# sensor-mega169a.net
KiCad netlist of a schematic drawn in EAGLE
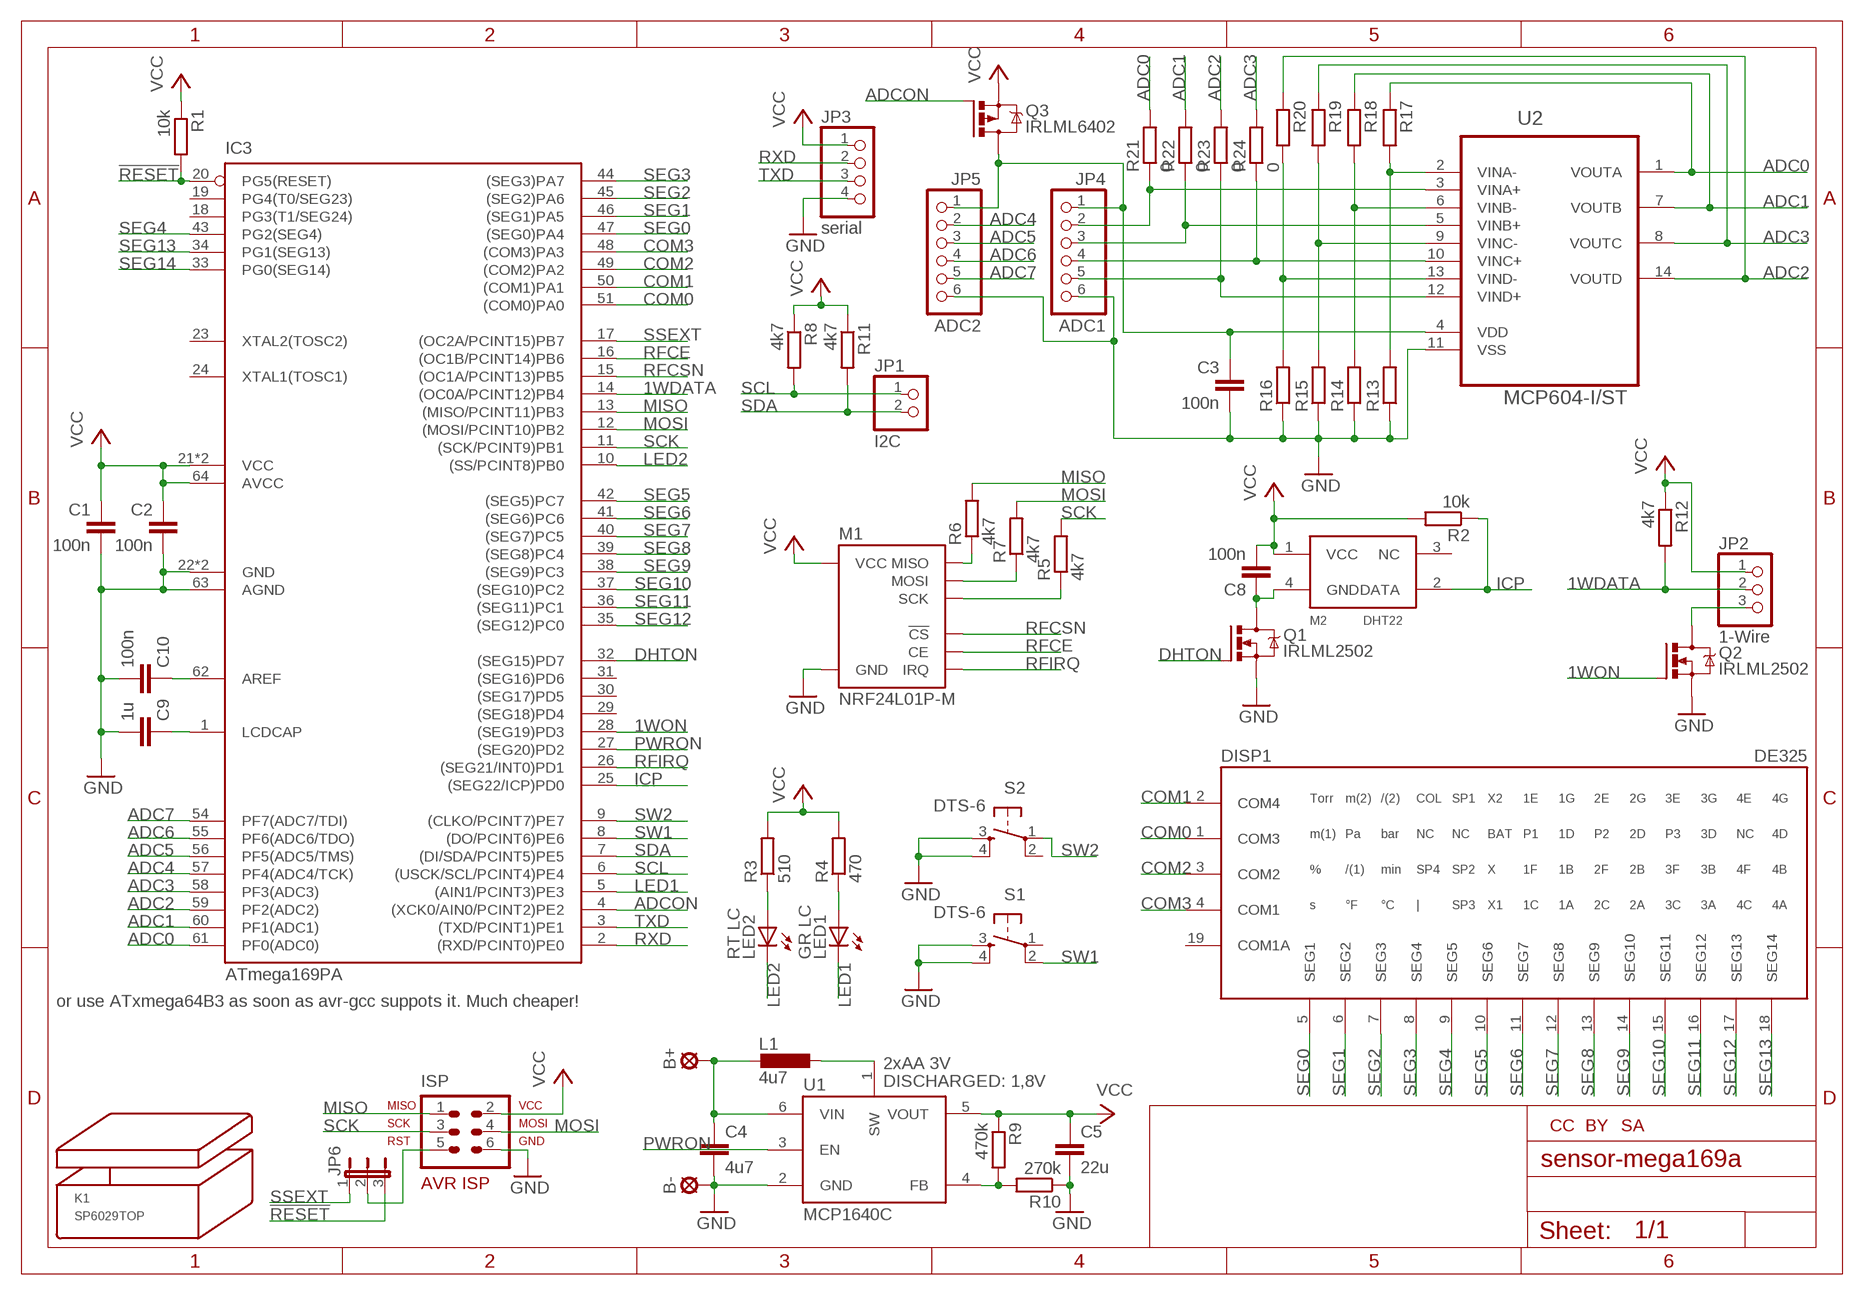
[diagram p0: schematic, sheet 1]

(export (version "E")
  (design (tool "Eeschema 10.0.6"))
  (components
    (comp (ref "B+")
      (value "LSP11")
      (footprint "eagle-import:LSP11")
      (libsource (lib "eagle-import") (part "LSP11"))
    )
    (comp (ref "B-")
      (value "LSP11")
      (footprint "eagle-import:LSP11")
      (libsource (lib "eagle-import") (part "LSP11"))
    )
    (comp (ref "C1")
      (value "100n")
      (footprint "eagle-import:C0603")
      (libsource (lib "eagle-import") (part "C-EUC0603"))
    )
    (comp (ref "C2")
      (value "100n")
      (footprint "eagle-import:C0603")
      (libsource (lib "eagle-import") (part "C-EUC0603"))
    )
    (comp (ref "C3")
      (value "100n")
      (footprint "eagle-import:C0603")
      (libsource (lib "eagle-import") (part "C-EUC0603"))
    )
    (comp (ref "C4")
      (value "4u7")
      (footprint "eagle-import:C0805")
      (libsource (lib "eagle-import") (part "C-EUC0805"))
    )
    (comp (ref "C5")
      (value "22u")
      (footprint "eagle-import:C1206")
      (libsource (lib "eagle-import") (part "C-EUC1206"))
    )
    (comp (ref "C8")
      (value "100n")
      (footprint "eagle-import:C0603")
      (libsource (lib "eagle-import") (part "C-EUC0603"))
    )
    (comp (ref "C9")
      (value "1u")
      (footprint "eagle-import:C0603")
      (libsource (lib "eagle-import") (part "C-EUC0603"))
    )
    (comp (ref "C10")
      (value "100n")
      (footprint "eagle-import:C0603")
      (libsource (lib "eagle-import") (part "C-EUC0603"))
    )
    (comp (ref "DISP1")
      (value "DE325")
      (footprint "eagle-import:DE325")
      (libsource (lib "eagle-import") (part "DE325"))
    )
    (comp (ref "IC3")
      (value "ATmega169PA")
      (footprint "eagle-import:TQFP64")
      (libsource (lib "eagle-import") (part "MEGA169-A"))
    )
    (comp (ref "ISP")
      (value "ML6")
      (footprint "eagle-import:AVR-ISP-6")
      (libsource (lib "eagle-import") (part "AVR-ISP-6VERT"))
    )
    (comp (ref "JP1")
      (value "I2C")
      (footprint "eagle-import:1X02")
      (libsource (lib "eagle-import") (part "PINHD-1X2_2.54"))
    )
    (comp (ref "JP2")
      (value "1-Wire")
      (footprint "eagle-import:1X03")
      (libsource (lib "eagle-import") (part "PINHD-1X3_2.54"))
    )
    (comp (ref "JP3")
      (value "serial")
      (footprint "eagle-import:1X04")
      (libsource (lib "eagle-import") (part "PINHD-1X4_2.54"))
    )
    (comp (ref "JP4")
      (value "ADC1")
      (footprint "eagle-import:1X06")
      (libsource (lib "eagle-import") (part "PINHD-1X6_2.54"))
    )
    (comp (ref "JP5")
      (value "ADC2")
      (footprint "eagle-import:1X06")
      (libsource (lib "eagle-import") (part "PINHD-1X6_2.54"))
    )
    (comp (ref "JP6")
      (value "JP2E")
      (footprint "eagle-import:JP2")
      (libsource (lib "eagle-import") (part "JP2E"))
    )
    (comp (ref "K1")
      (value "SP6029TOP")
      (footprint "eagle-import:SP6029T")
      (libsource (lib "eagle-import") (part "SP6029TOP"))
    )
    (comp (ref "L1")
      (value "4u7")
      (footprint "eagle-import:PISG")
      (libsource (lib "eagle-import") (part "L-EUPISG"))
    )
    (comp (ref "LED1")
      (value "GR LC")
      (footprint "eagle-import:LED5MM")
      (libsource (lib "eagle-import") (part "LED5MM"))
    )
    (comp (ref "LED2")
      (value "RT LC")
      (footprint "eagle-import:LED5MM")
      (libsource (lib "eagle-import") (part "LED5MM"))
    )
    (comp (ref "M1")
      (value "NRF24L01P-M")
      (footprint "eagle-import:NRF24L01P-A")
      (libsource (lib "eagle-import") (part "NRF24L01P-M"))
    )
    (comp (ref "M2")
      (value "DHT22")
      (footprint "eagle-import:DHT22")
      (libsource (lib "eagle-import") (part "DHT22"))
    )
    (comp (ref "Q1")
      (value "IRLML2502")
      (footprint "eagle-import:MICRO3")
      (libsource (lib "eagle-import") (part "IRLML2502"))
    )
    (comp (ref "Q2")
      (value "IRLML2502")
      (footprint "eagle-import:MICRO3")
      (libsource (lib "eagle-import") (part "IRLML2502"))
    )
    (comp (ref "Q3")
      (value "IRLML6402")
      (footprint "eagle-import:MICRO3")
      (libsource (lib "eagle-import") (part "IRLML6402"))
    )
    (comp (ref "R1")
      (value "10k")
      (footprint "eagle-import:R0603")
      (libsource (lib "eagle-import") (part "R-EU_R0603"))
    )
    (comp (ref "R2")
      (value "10k")
      (footprint "eagle-import:R0603")
      (libsource (lib "eagle-import") (part "R-EU_R0603"))
    )
    (comp (ref "R3")
      (value "510")
      (footprint "eagle-import:R0805")
      (libsource (lib "eagle-import") (part "R-EU_R0805"))
    )
    (comp (ref "R4")
      (value "470")
      (footprint "eagle-import:R0805")
      (libsource (lib "eagle-import") (part "R-EU_R0805"))
    )
    (comp (ref "R5")
      (value "4k7")
      (footprint "eagle-import:R0603")
      (libsource (lib "eagle-import") (part "R-EU_R0603"))
    )
    (comp (ref "R6")
      (value "4k7")
      (footprint "eagle-import:R0603")
      (libsource (lib "eagle-import") (part "R-EU_R0603"))
    )
    (comp (ref "R7")
      (value "4k7")
      (footprint "eagle-import:R0603")
      (libsource (lib "eagle-import") (part "R-EU_R0603"))
    )
    (comp (ref "R8")
      (value "4k7")
      (footprint "eagle-import:R0603")
      (libsource (lib "eagle-import") (part "R-EU_R0603"))
    )
    (comp (ref "R9")
      (value "470k")
      (footprint "eagle-import:R0603")
      (libsource (lib "eagle-import") (part "R-EU_R0603"))
    )
    (comp (ref "R10")
      (value "270k")
      (footprint "eagle-import:R0603")
      (libsource (lib "eagle-import") (part "R-EU_R0603"))
    )
    (comp (ref "R11")
      (value "4k7")
      (footprint "eagle-import:R0603")
      (libsource (lib "eagle-import") (part "R-EU_R0603"))
    )
    (comp (ref "R12")
      (value "4k7")
      (footprint "eagle-import:R0603")
      (libsource (lib "eagle-import") (part "R-EU_R0603"))
    )
    (comp (ref "R13")
      (value "R-EU_R0603")
      (footprint "eagle-import:R0603")
      (libsource (lib "eagle-import") (part "R-EU_R0603"))
    )
    (comp (ref "R14")
      (value "R-EU_R0603")
      (footprint "eagle-import:R0603")
      (libsource (lib "eagle-import") (part "R-EU_R0603"))
    )
    (comp (ref "R15")
      (value "R-EU_R0603")
      (footprint "eagle-import:R0603")
      (libsource (lib "eagle-import") (part "R-EU_R0603"))
    )
    (comp (ref "R16")
      (value "R-EU_R0603")
      (footprint "eagle-import:R0603")
      (libsource (lib "eagle-import") (part "R-EU_R0603"))
    )
    (comp (ref "R17")
      (value "R-EU_R0603")
      (footprint "eagle-import:R0603")
      (libsource (lib "eagle-import") (part "R-EU_R0603"))
    )
    (comp (ref "R18")
      (value "R-EU_R0603")
      (footprint "eagle-import:R0603")
      (libsource (lib "eagle-import") (part "R-EU_R0603"))
    )
    (comp (ref "R19")
      (value "R-EU_R0603")
      (footprint "eagle-import:R0603")
      (libsource (lib "eagle-import") (part "R-EU_R0603"))
    )
    (comp (ref "R20")
      (value "R-EU_R0603")
      (footprint "eagle-import:R0603")
      (libsource (lib "eagle-import") (part "R-EU_R0603"))
    )
    (comp (ref "R21")
      (value "0")
      (footprint "eagle-import:R0201")
      (libsource (lib "eagle-import") (part "R-EU_R0201"))
    )
    (comp (ref "R22")
      (value "0")
      (footprint "eagle-import:R0201")
      (libsource (lib "eagle-import") (part "R-EU_R0201"))
    )
    (comp (ref "R23")
      (value "0")
      (footprint "eagle-import:R0201")
      (libsource (lib "eagle-import") (part "R-EU_R0201"))
    )
    (comp (ref "R24")
      (value "0")
      (footprint "eagle-import:R0201")
      (libsource (lib "eagle-import") (part "R-EU_R0201"))
    )
    (comp (ref "S1")
      (value "DTS-6")
      (footprint "eagle-import:DTS-6")
      (libsource (lib "eagle-import") (part "DTS-6"))
    )
    (comp (ref "S2")
      (value "DTS-6")
      (footprint "eagle-import:DTS-6")
      (libsource (lib "eagle-import") (part "DTS-6"))
    )
    (comp (ref "U$1")
      (value "CC-TPLACE-HALF")
      (footprint "eagle-import:CC_TPLACE_HS")
      (libsource (lib "eagle-import") (part "CC-TPLACE-HALF"))
    )
    (comp (ref "U$3")
      (value "BY-TPLACE-HS")
      (footprint "eagle-import:BY_TPLACE_HS")
      (libsource (lib "eagle-import") (part "BY-TPLACE-HS"))
    )
    (comp (ref "U$4")
      (value "SA-TPLACE-HALF")
      (footprint "eagle-import:SA_TPLACE_HS")
      (libsource (lib "eagle-import") (part "SA-TPLACE-HALF"))
    )
    (comp (ref "U1")
      (value "MCP1640C")
      (footprint "eagle-import:SOT23-6")
      (libsource (lib "eagle-import") (part "MCP1640"))
    )
    (comp (ref "U2")
      (value "MCP604-I/ST")
      (footprint "eagle-import:SOP65P640X120-14N")
      (libsource (lib "eagle-import") (part "MCP604-I/ST"))
    )
  )
  (nets
    (net (code "1") (name "/1WDATA") (class "Default")
      (node (ref "IC3") (pin "14") (pinfunction "(OC0A/PCINT12)PB4_14") (pintype "bidirectional"))
      (node (ref "JP2") (pin "2") (pinfunction "2_2") (pintype "passive"))
      (node (ref "R12") (pin "2") (pinfunction "2_2") (pintype "passive"))
    )
    (net (code "2") (name "/1WON") (class "Default")
      (node (ref "IC3") (pin "28") (pinfunction "(SEG19)PD3_28") (pintype "bidirectional"))
      (node (ref "Q2") (pin "1") (pinfunction "G_1") (pintype "passive"))
    )
    (net (code "3") (name "/ADC0") (class "Default")
      (node (ref "IC3") (pin "61") (pinfunction "PF0(ADC0)_61") (pintype "input"))
      (node (ref "R17") (pin "1") (pinfunction "1_1") (pintype "passive"))
      (node (ref "R21") (pin "2") (pinfunction "2_2") (pintype "passive"))
      (node (ref "U2") (pin "1") (pinfunction "VOUTA_1") (pintype "output"))
    )
    (net (code "4") (name "/ADC1") (class "Default")
      (node (ref "IC3") (pin "60") (pinfunction "PF1(ADC1)_60") (pintype "input"))
      (node (ref "R18") (pin "1") (pinfunction "1_1") (pintype "passive"))
      (node (ref "R22") (pin "2") (pinfunction "2_2") (pintype "passive"))
      (node (ref "U2") (pin "7") (pinfunction "VOUTB_7") (pintype "output"))
    )
    (net (code "5") (name "/ADC2") (class "Default")
      (node (ref "IC3") (pin "59") (pinfunction "PF2(ADC2)_59") (pintype "input"))
      (node (ref "R20") (pin "1") (pinfunction "1_1") (pintype "passive"))
      (node (ref "R23") (pin "2") (pinfunction "2_2") (pintype "passive"))
      (node (ref "U2") (pin "14") (pinfunction "VOUTD_14") (pintype "output"))
    )
    (net (code "6") (name "/ADC3") (class "Default")
      (node (ref "IC3") (pin "58") (pinfunction "PF3(ADC3)_58") (pintype "input"))
      (node (ref "R19") (pin "1") (pinfunction "1_1") (pintype "passive"))
      (node (ref "R24") (pin "2") (pinfunction "2_2") (pintype "passive"))
      (node (ref "U2") (pin "8") (pinfunction "VOUTC_8") (pintype "output"))
    )
    (net (code "7") (name "/ADC4") (class "Default")
      (node (ref "IC3") (pin "57") (pinfunction "PF4(ADC4/TCK)_57") (pintype "input"))
      (node (ref "JP5") (pin "2") (pinfunction "2_2") (pintype "passive"))
    )
    (net (code "8") (name "/ADC5") (class "Default")
      (node (ref "IC3") (pin "56") (pinfunction "PF5(ADC5/TMS)_56") (pintype "input"))
      (node (ref "JP5") (pin "3") (pinfunction "3_3") (pintype "passive"))
    )
    (net (code "9") (name "/ADC6") (class "Default")
      (node (ref "IC3") (pin "55") (pinfunction "PF6(ADC6/TDO)_55") (pintype "input"))
      (node (ref "JP5") (pin "4") (pinfunction "4_4") (pintype "passive"))
    )
    (net (code "10") (name "/ADC7") (class "Default")
      (node (ref "IC3") (pin "54") (pinfunction "PF7(ADC7/TDI)_54") (pintype "input"))
      (node (ref "JP5") (pin "5") (pinfunction "5_5") (pintype "passive"))
    )
    (net (code "11") (name "/ADCON") (class "Default")
      (node (ref "IC3") (pin "4") (pinfunction "(XCK0/AIN0/PCINT2)PE2_4") (pintype "bidirectional"))
      (node (ref "Q3") (pin "1") (pinfunction "G_1") (pintype "passive"))
    )
    (net (code "12") (name "/COM0") (class "Default")
      (node (ref "DISP1") (pin "1") (pinfunction "COM3_1") (pintype "input"))
      (node (ref "IC3") (pin "51") (pinfunction "(COM0)PA0_51") (pintype "bidirectional"))
    )
    (net (code "13") (name "/COM1") (class "Default")
      (node (ref "DISP1") (pin "2") (pinfunction "COM4_2") (pintype "input"))
      (node (ref "IC3") (pin "50") (pinfunction "(COM1)PA1_50") (pintype "bidirectional"))
    )
    (net (code "14") (name "/COM2") (class "Default")
      (node (ref "DISP1") (pin "3") (pinfunction "COM2_3") (pintype "input"))
      (node (ref "IC3") (pin "49") (pinfunction "(COM2)PA2_49") (pintype "bidirectional"))
    )
    (net (code "15") (name "/COM3") (class "Default")
      (node (ref "DISP1") (pin "4") (pinfunction "COM1_4") (pintype "input"))
      (node (ref "IC3") (pin "48") (pinfunction "(COM3)PA3_48") (pintype "bidirectional"))
    )
    (net (code "16") (name "/DHTON") (class "Default")
      (node (ref "IC3") (pin "32") (pinfunction "(SEG15)PD7_32") (pintype "bidirectional"))
      (node (ref "Q1") (pin "1") (pinfunction "G_1") (pintype "passive"))
    )
    (net (code "17") (name "/ICP") (class "Default")
      (node (ref "IC3") (pin "25") (pinfunction "(SEG22/ICP)PD0_25") (pintype "bidirectional"))
      (node (ref "M2") (pin "2") (pinfunction "DATA_2") (pintype "bidirectional"))
      (node (ref "R2") (pin "1") (pinfunction "1_1") (pintype "passive"))
    )
    (net (code "18") (name "/LED1") (class "Default")
      (node (ref "IC3") (pin "5") (pinfunction "(AIN1/PCINT3)PE3_5") (pintype "bidirectional"))
      (node (ref "LED1") (pin "K") (pinfunction "C_K") (pintype "passive"))
    )
    (net (code "19") (name "/LED2") (class "Default")
      (node (ref "IC3") (pin "10") (pinfunction "(SS/PCINT8)PB0_10") (pintype "bidirectional"))
      (node (ref "LED2") (pin "K") (pinfunction "C_K") (pintype "passive"))
    )
    (net (code "20") (name "/MISO") (class "Default")
      (node (ref "IC3") (pin "13") (pinfunction "(MISO/PCINT11)PB3_13") (pintype "bidirectional"))
      (node (ref "ISP") (pin "1") (pinfunction "1_1") (pintype "passive"))
      (node (ref "R6") (pin "2") (pinfunction "2_2") (pintype "passive"))
    )
    (net (code "21") (name "/MOSI") (class "Default")
      (node (ref "IC3") (pin "12") (pinfunction "(MOSI/PCINT10)PB2_12") (pintype "bidirectional"))
      (node (ref "ISP") (pin "4") (pinfunction "4_4") (pintype "passive"))
      (node (ref "R7") (pin "2") (pinfunction "2_2") (pintype "passive"))
    )
    (net (code "22") (name "/PWRON") (class "Default")
      (node (ref "IC3") (pin "27") (pinfunction "(SEG20)PD2_27") (pintype "bidirectional"))
      (node (ref "U1") (pin "3") (pinfunction "EN_3") (pintype "input"))
    )
    (net (code "23") (name "/RFCE") (class "Default")
      (node (ref "IC3") (pin "16") (pinfunction "(OC1B/PCINT14)PB6_16") (pintype "bidirectional"))
      (node (ref "M1") (pin "CE") (pinfunction "CE_CE") (pintype "input"))
    )
    (net (code "24") (name "/RFCSN") (class "Default")
      (node (ref "IC3") (pin "15") (pinfunction "(OC1A/PCINT13)PB5_15") (pintype "bidirectional"))
      (node (ref "M1") (pin "CSN") (pinfunction "~{CS}_CSN") (pintype "input"))
    )
    (net (code "25") (name "/RFIRQ") (class "Default")
      (node (ref "IC3") (pin "26") (pinfunction "(SEG21/INT0)PD1_26") (pintype "bidirectional"))
      (node (ref "M1") (pin "IRQ") (pinfunction "IRQ_IRQ") (pintype "output"))
    )
    (net (code "26") (name "/RXD") (class "Default")
      (node (ref "IC3") (pin "2") (pinfunction "(RXD/PCINT0)PE0_2") (pintype "bidirectional"))
      (node (ref "JP3") (pin "2") (pinfunction "2_2") (pintype "passive"))
    )
    (net (code "27") (name "/SCK") (class "Default")
      (node (ref "IC3") (pin "11") (pinfunction "(SCK/PCINT9)PB1_11") (pintype "bidirectional"))
      (node (ref "ISP") (pin "3") (pinfunction "3_3") (pintype "passive"))
      (node (ref "R5") (pin "2") (pinfunction "2_2") (pintype "passive"))
    )
    (net (code "28") (name "/SCL") (class "Default")
      (node (ref "IC3") (pin "6") (pinfunction "(USCK/SCL/PCINT4)PE4_6") (pintype "bidirectional"))
      (node (ref "JP1") (pin "1") (pinfunction "1_1") (pintype "passive"))
      (node (ref "R8") (pin "2") (pinfunction "2_2") (pintype "passive"))
    )
    (net (code "29") (name "/SDA") (class "Default")
      (node (ref "IC3") (pin "7") (pinfunction "(DI/SDA/PCINT5)PE5_7") (pintype "bidirectional"))
      (node (ref "JP1") (pin "2") (pinfunction "2_2") (pintype "passive"))
      (node (ref "R11") (pin "2") (pinfunction "2_2") (pintype "passive"))
    )
    (net (code "30") (name "/SEG0") (class "Default")
      (node (ref "DISP1") (pin "5") (pinfunction "SEG1_5") (pintype "input"))
      (node (ref "IC3") (pin "47") (pinfunction "(SEG0)PA4_47") (pintype "bidirectional"))
    )
    (net (code "31") (name "/SEG1") (class "Default")
      (node (ref "DISP1") (pin "6") (pinfunction "SEG2_6") (pintype "input"))
      (node (ref "IC3") (pin "46") (pinfunction "(SEG1)PA5_46") (pintype "bidirectional"))
    )
    (net (code "32") (name "/SEG2") (class "Default")
      (node (ref "DISP1") (pin "7") (pinfunction "SEG3_7") (pintype "input"))
      (node (ref "IC3") (pin "45") (pinfunction "(SEG2)PA6_45") (pintype "bidirectional"))
    )
    (net (code "33") (name "/SEG3") (class "Default")
      (node (ref "DISP1") (pin "8") (pinfunction "SEG4_8") (pintype "input"))
      (node (ref "IC3") (pin "44") (pinfunction "(SEG3)PA7_44") (pintype "bidirectional"))
    )
    (net (code "34") (name "/SEG4") (class "Default")
      (node (ref "DISP1") (pin "9") (pinfunction "SEG5_9") (pintype "input"))
      (node (ref "IC3") (pin "43") (pinfunction "PG2(SEG4)_43") (pintype "bidirectional"))
    )
    (net (code "35") (name "/SEG5") (class "Default")
      (node (ref "DISP1") (pin "10") (pinfunction "SEG6_10") (pintype "input"))
      (node (ref "IC3") (pin "42") (pinfunction "(SEG5)PC7_42") (pintype "output"))
    )
    (net (code "36") (name "/SEG6") (class "Default")
      (node (ref "DISP1") (pin "11") (pinfunction "SEG7_11") (pintype "input"))
      (node (ref "IC3") (pin "41") (pinfunction "(SEG6)PC6_41") (pintype "output"))
    )
    (net (code "37") (name "/SEG7") (class "Default")
      (node (ref "DISP1") (pin "12") (pinfunction "SEG8_12") (pintype "input"))
      (node (ref "IC3") (pin "40") (pinfunction "(SEG7)PC5_40") (pintype "output"))
    )
    (net (code "38") (name "/SEG8") (class "Default")
      (node (ref "DISP1") (pin "13") (pinfunction "SEG9_13") (pintype "input"))
      (node (ref "IC3") (pin "39") (pinfunction "(SEG8)PC4_39") (pintype "output"))
    )
    (net (code "39") (name "/SEG9") (class "Default")
      (node (ref "DISP1") (pin "14") (pinfunction "SEG10_14") (pintype "input"))
      (node (ref "IC3") (pin "38") (pinfunction "(SEG9)PC3_38") (pintype "output"))
    )
    (net (code "40") (name "/SEG10") (class "Default")
      (node (ref "DISP1") (pin "15") (pinfunction "SEG11_15") (pintype "input"))
      (node (ref "IC3") (pin "37") (pinfunction "(SEG10)PC2_37") (pintype "output"))
    )
    (net (code "41") (name "/SEG11") (class "Default")
      (node (ref "DISP1") (pin "16") (pinfunction "SEG12_16") (pintype "input"))
      (node (ref "IC3") (pin "36") (pinfunction "(SEG11)PC1_36") (pintype "output"))
    )
    (net (code "42") (name "/SEG12") (class "Default")
      (node (ref "DISP1") (pin "17") (pinfunction "SEG13_17") (pintype "input"))
      (node (ref "IC3") (pin "35") (pinfunction "(SEG12)PC0_35") (pintype "output"))
    )
    (net (code "43") (name "/SEG13") (class "Default")
      (node (ref "DISP1") (pin "18") (pinfunction "SEG14_18") (pintype "input"))
      (node (ref "IC3") (pin "34") (pinfunction "PG1(SEG13)_34") (pintype "bidirectional"))
    )
    (net (code "44") (name "/SEG14") (class "Default")
      (node (ref "IC3") (pin "33") (pinfunction "PG0(SEG14)_33") (pintype "bidirectional"))
    )
    (net (code "45") (name "/SSEXT") (class "Default")
      (node (ref "IC3") (pin "17") (pinfunction "(OC2A/PCINT15)PB7_17") (pintype "bidirectional"))
      (node (ref "JP6") (pin "1") (pinfunction "1_1") (pintype "passive"))
    )
    (net (code "46") (name "/SW1") (class "Default")
      (node (ref "IC3") (pin "8") (pinfunction "(DO/PCINT6)PE6_8") (pintype "bidirectional"))
      (node (ref "S1") (pin "2") (pinfunction "2_2") (pintype "passive"))
    )
    (net (code "47") (name "/SW2") (class "Default")
      (node (ref "IC3") (pin "9") (pinfunction "(CLKO/PCINT7)PE7_9") (pintype "bidirectional"))
      (node (ref "S2") (pin "1") (pinfunction "1_1") (pintype "passive"))
    )
    (net (code "48") (name "/TXD") (class "Default")
      (node (ref "IC3") (pin "3") (pinfunction "(TXD/PCINT1)PE1_3") (pintype "bidirectional"))
      (node (ref "JP3") (pin "3") (pinfunction "3_3") (pintype "passive"))
    )
    (net (code "49") (name "/~{RESET}") (class "Default")
      (node (ref "IC3") (pin "20") (pinfunction "PG5(RESET)_20") (pintype "input"))
      (node (ref "JP6") (pin "3") (pinfunction "3_3") (pintype "passive"))
      (node (ref "R1") (pin "2") (pinfunction "2_2") (pintype "passive"))
    )
    (net (code "50") (name "GND") (class "Default")
      (node (ref "B-") (pin "MP") (pinfunction "MP_MP") (pintype "passive"))
      (node (ref "C1") (pin "2") (pinfunction "2_2") (pintype "passive"))
      (node (ref "C10") (pin "2") (pinfunction "2_2") (pintype "passive"))
      (node (ref "C2") (pin "2") (pinfunction "2_2") (pintype "passive"))
      (node (ref "C3") (pin "2") (pinfunction "2_2") (pintype "passive"))
      (node (ref "C4") (pin "2") (pinfunction "2_2") (pintype "passive"))
      (node (ref "C5") (pin "2") (pinfunction "2_2") (pintype "passive"))
      (node (ref "C9") (pin "2") (pinfunction "2_2") (pintype "passive"))
      (node (ref "IC3") (pin "22") (pinfunction "GND_22") (pintype "power_in"))
      (node (ref "IC3") (pin "53") (pinfunction "GND_53") (pintype "power_in"))
      (node (ref "IC3") (pin "63") (pinfunction "AGND_63") (pintype "power_in"))
      (node (ref "ISP") (pin "6") (pinfunction "6_6") (pintype "passive"))
      (node (ref "JP3") (pin "4") (pinfunction "4_4") (pintype "passive"))
      (node (ref "JP4") (pin "6") (pinfunction "6_6") (pintype "passive"))
      (node (ref "JP5") (pin "6") (pinfunction "6_6") (pintype "passive"))
      (node (ref "M1") (pin "GND_A") (pinfunction "GND_GND_A") (pintype "power_in"))
      (node (ref "M1") (pin "GND_B") (pinfunction "GND_GND_B") (pintype "power_in"))
      (node (ref "Q1") (pin "2") (pinfunction "S_2") (pintype "passive"))
      (node (ref "Q2") (pin "2") (pinfunction "S_2") (pintype "passive"))
      (node (ref "R10") (pin "1") (pinfunction "1_1") (pintype "passive"))
      (node (ref "R13") (pin "1") (pinfunction "1_1") (pintype "passive"))
      (node (ref "R14") (pin "1") (pinfunction "1_1") (pintype "passive"))
      (node (ref "R15") (pin "1") (pinfunction "1_1") (pintype "passive"))
      (node (ref "R16") (pin "1") (pinfunction "1_1") (pintype "passive"))
      (node (ref "S1") (pin "3") (pinfunction "3_3") (pintype "passive"))
      (node (ref "S1") (pin "4") (pinfunction "4_4") (pintype "passive"))
      (node (ref "S2") (pin "3") (pinfunction "3_3") (pintype "passive"))
      (node (ref "S2") (pin "4") (pinfunction "4_4") (pintype "passive"))
      (node (ref "U1") (pin "2") (pinfunction "GND_2") (pintype "power_in"))
      (node (ref "U2") (pin "11") (pinfunction "VSS_11") (pintype "passive"))
    )
    (net (code "51") (name "Net-(IC3-AREF)") (class "Default")
      (node (ref "C10") (pin "1") (pinfunction "1_1") (pintype "passive"))
      (node (ref "IC3") (pin "62") (pinfunction "AREF_62") (pintype "bidirectional"))
    )
    (net (code "52") (name "Net-(IC3-LCDCAP)") (class "Default")
      (node (ref "C9") (pin "1") (pinfunction "1_1") (pintype "passive"))
      (node (ref "IC3") (pin "1") (pinfunction "LCDCAP_1") (pintype "input"))
    )
    (net (code "53") (name "Net-(ISP-Pad5)") (class "Default")
      (node (ref "ISP") (pin "5") (pinfunction "5_5") (pintype "passive"))
      (node (ref "JP6") (pin "2") (pinfunction "2_2") (pintype "passive"))
    )
    (net (code "54") (name "Net-(LED1-PadA)") (class "Default")
      (node (ref "LED1") (pin "A") (pinfunction "A_A") (pintype "passive"))
      (node (ref "R4") (pin "1") (pinfunction "1_1") (pintype "passive"))
    )
    (net (code "55") (name "Net-(LED2-PadA)") (class "Default")
      (node (ref "LED2") (pin "A") (pinfunction "A_A") (pintype "passive"))
      (node (ref "R3") (pin "1") (pinfunction "1_1") (pintype "passive"))
    )
    (net (code "56") (name "Net-(M1-PadMISO)") (class "Default")
      (node (ref "M1") (pin "MISO") (pinfunction "MISO_MISO") (pintype "output"))
      (node (ref "R6") (pin "1") (pinfunction "1_1") (pintype "passive"))
    )
    (net (code "57") (name "Net-(M1-PadMOSI)") (class "Default")
      (node (ref "M1") (pin "MOSI") (pinfunction "MOSI_MOSI") (pintype "input"))
      (node (ref "R7") (pin "1") (pinfunction "1_1") (pintype "passive"))
    )
    (net (code "58") (name "Net-(M1-PadSCK)") (class "Default")
      (node (ref "M1") (pin "SCK") (pinfunction "SCK_SCK") (pintype "bidirectional"))
      (node (ref "R5") (pin "1") (pinfunction "1_1") (pintype "passive"))
    )
    (net (code "59") (name "Net-(M2-GND)") (class "Default")
      (node (ref "C8") (pin "1") (pinfunction "1_1") (pintype "passive"))
      (node (ref "M2") (pin "4") (pinfunction "GND_4") (pintype "power_in"))
      (node (ref "Q1") (pin "3") (pinfunction "D_3") (pintype "passive"))
    )
    (net (code "60") (name "Net-(Q2-D)") (class "Default")
      (node (ref "JP2") (pin "3") (pinfunction "3_3") (pintype "passive"))
      (node (ref "Q2") (pin "3") (pinfunction "D_3") (pintype "passive"))
    )
    (net (code "61") (name "Net-(Q3-D)") (class "Default")
      (node (ref "C3") (pin "1") (pinfunction "1_1") (pintype "passive"))
      (node (ref "JP4") (pin "1") (pinfunction "1_1") (pintype "passive"))
      (node (ref "JP5") (pin "1") (pinfunction "1_1") (pintype "passive"))
      (node (ref "Q3") (pin "3") (pinfunction "D_3") (pintype "passive"))
      (node (ref "U2") (pin "4") (pinfunction "VDD_4") (pintype "power_in"))
    )
    (net (code "62") (name "Net-(U1-FB)") (class "Default")
      (node (ref "R10") (pin "2") (pinfunction "2_2") (pintype "passive"))
      (node (ref "R9") (pin "2") (pinfunction "2_2") (pintype "passive"))
      (node (ref "U1") (pin "4") (pinfunction "FB_4") (pintype "input"))
    )
    (net (code "63") (name "Net-(U1-SW)") (class "Default")
      (node (ref "L1") (pin "1") (pinfunction "1_1") (pintype "passive"))
      (node (ref "U1") (pin "1") (pinfunction "SW_1") (pintype "passive"))
    )
    (net (code "64") (name "Net-(U1-VIN)") (class "Default")
      (node (ref "B+") (pin "MP") (pinfunction "MP_MP") (pintype "passive"))
      (node (ref "C4") (pin "1") (pinfunction "1_1") (pintype "passive"))
      (node (ref "L1") (pin "2") (pinfunction "2_2") (pintype "passive"))
      (node (ref "U1") (pin "6") (pinfunction "VIN_6") (pintype "power_in"))
    )
    (net (code "65") (name "Net-(U2-VINA+)") (class "Default")
      (node (ref "JP4") (pin "2") (pinfunction "2_2") (pintype "passive"))
      (node (ref "R21") (pin "1") (pinfunction "1_1") (pintype "passive"))
      (node (ref "U2") (pin "3") (pinfunction "VINA+_3") (pintype "input"))
    )
    (net (code "66") (name "Net-(U2-VINA-)") (class "Default")
      (node (ref "R13") (pin "2") (pinfunction "2_2") (pintype "passive"))
      (node (ref "R17") (pin "2") (pinfunction "2_2") (pintype "passive"))
      (node (ref "U2") (pin "2") (pinfunction "VINA-_2") (pintype "input"))
    )
    (net (code "67") (name "Net-(U2-VINB+)") (class "Default")
      (node (ref "JP4") (pin "3") (pinfunction "3_3") (pintype "passive"))
      (node (ref "R22") (pin "1") (pinfunction "1_1") (pintype "passive"))
      (node (ref "U2") (pin "5") (pinfunction "VINB+_5") (pintype "input"))
    )
    (net (code "68") (name "Net-(U2-VINB-)") (class "Default")
      (node (ref "R14") (pin "2") (pinfunction "2_2") (pintype "passive"))
      (node (ref "R18") (pin "2") (pinfunction "2_2") (pintype "passive"))
      (node (ref "U2") (pin "6") (pinfunction "VINB-_6") (pintype "input"))
    )
    (net (code "69") (name "Net-(U2-VINC+)") (class "Default")
      (node (ref "JP4") (pin "4") (pinfunction "4_4") (pintype "passive"))
      (node (ref "R24") (pin "1") (pinfunction "1_1") (pintype "passive"))
      (node (ref "U2") (pin "10") (pinfunction "VINC+_10") (pintype "input"))
    )
    (net (code "70") (name "Net-(U2-VINC-)") (class "Default")
      (node (ref "R15") (pin "2") (pinfunction "2_2") (pintype "passive"))
      (node (ref "R19") (pin "2") (pinfunction "2_2") (pintype "passive"))
      (node (ref "U2") (pin "9") (pinfunction "VINC-_9") (pintype "input"))
    )
    (net (code "71") (name "Net-(U2-VIND+)") (class "Default")
      (node (ref "JP4") (pin "5") (pinfunction "5_5") (pintype "passive"))
      (node (ref "R23") (pin "1") (pinfunction "1_1") (pintype "passive"))
      (node (ref "U2") (pin "12") (pinfunction "VIND+_12") (pintype "input"))
    )
    (net (code "72") (name "Net-(U2-VIND-)") (class "Default")
      (node (ref "R16") (pin "2") (pinfunction "2_2") (pintype "passive"))
      (node (ref "R20") (pin "2") (pinfunction "2_2") (pintype "passive"))
      (node (ref "U2") (pin "13") (pinfunction "VIND-_13") (pintype "input"))
    )
    (net (code "73") (name "VCC") (class "Default")
      (node (ref "C1") (pin "1") (pinfunction "1_1") (pintype "passive"))
      (node (ref "C2") (pin "1") (pinfunction "1_1") (pintype "passive"))
      (node (ref "C5") (pin "1") (pinfunction "1_1") (pintype "passive"))
      (node (ref "C8") (pin "2") (pinfunction "2_2") (pintype "passive"))
      (node (ref "IC3") (pin "21") (pinfunction "VCC_21") (pintype "power_in"))
      (node (ref "IC3") (pin "52") (pinfunction "VCC_52") (pintype "power_in"))
      (node (ref "IC3") (pin "64") (pinfunction "AVCC_64") (pintype "power_in"))
      (node (ref "ISP") (pin "2") (pinfunction "2_2") (pintype "passive"))
      (node (ref "JP2") (pin "1") (pinfunction "1_1") (pintype "passive"))
      (node (ref "JP3") (pin "1") (pinfunction "1_1") (pintype "passive"))
      (node (ref "M1") (pin "VCC_A") (pinfunction "VCC_VCC_A") (pintype "power_in"))
      (node (ref "M1") (pin "VCC_B") (pinfunction "VCC_VCC_B") (pintype "power_in"))
      (node (ref "M2") (pin "1") (pinfunction "VCC_1") (pintype "power_in"))
      (node (ref "Q3") (pin "2") (pinfunction "S_2") (pintype "passive"))
      (node (ref "R1") (pin "1") (pinfunction "1_1") (pintype "passive"))
      (node (ref "R11") (pin "1") (pinfunction "1_1") (pintype "passive"))
      (node (ref "R12") (pin "1") (pinfunction "1_1") (pintype "passive"))
      (node (ref "R2") (pin "2") (pinfunction "2_2") (pintype "passive"))
      (node (ref "R3") (pin "2") (pinfunction "2_2") (pintype "passive"))
      (node (ref "R4") (pin "2") (pinfunction "2_2") (pintype "passive"))
      (node (ref "R8") (pin "1") (pinfunction "1_1") (pintype "passive"))
      (node (ref "R9") (pin "1") (pinfunction "1_1") (pintype "passive"))
      (node (ref "U1") (pin "5") (pinfunction "VOUT_5") (pintype "power_in"))
    )
    (net (code "74") (name "unconnected-(DISP1-COM1A-Pad19)") (class "Default")
      (node (ref "DISP1") (pin "19") (pinfunction "COM1A_19") (pintype "input"))
    )
    (net (code "75") (name "unconnected-(IC3-(SEG16)PD6-Pad31)") (class "Default")
      (node (ref "IC3") (pin "31") (pinfunction "(SEG16)PD6_31") (pintype "bidirectional"))
    )
    (net (code "76") (name "unconnected-(IC3-(SEG17)PD5-Pad30)") (class "Default")
      (node (ref "IC3") (pin "30") (pinfunction "(SEG17)PD5_30") (pintype "bidirectional"))
    )
    (net (code "77") (name "unconnected-(IC3-(SEG18)PD4-Pad29)") (class "Default")
      (node (ref "IC3") (pin "29") (pinfunction "(SEG18)PD4_29") (pintype "bidirectional"))
    )
    (net (code "78") (name "unconnected-(IC3-PG3(T1{slash}SEG24)-Pad18)") (class "Default")
      (node (ref "IC3") (pin "18") (pinfunction "PG3(T1/SEG24)_18") (pintype "bidirectional"))
    )
    (net (code "79") (name "unconnected-(IC3-PG4(T0{slash}SEG23)-Pad19)") (class "Default")
      (node (ref "IC3") (pin "19") (pinfunction "PG4(T0/SEG23)_19") (pintype "bidirectional"))
    )
    (net (code "80") (name "unconnected-(IC3-XTAL1(TOSC1)-Pad24)") (class "Default")
      (node (ref "IC3") (pin "24") (pinfunction "XTAL1(TOSC1)_24") (pintype "bidirectional"))
    )
    (net (code "81") (name "unconnected-(IC3-XTAL2(TOSC2)-Pad23)") (class "Default")
      (node (ref "IC3") (pin "23") (pinfunction "XTAL2(TOSC2)_23") (pintype "bidirectional"))
    )
    (net (code "82") (name "unconnected-(M2-NC-Pad3)") (class "Default")
      (node (ref "M2") (pin "3") (pinfunction "NC_3") (pintype "no_connect"))
    )
    (net (code "83") (name "unconnected-(S1-Pad1)") (class "Default")
      (node (ref "S1") (pin "1") (pinfunction "1_1") (pintype "passive"))
    )
    (net (code "84") (name "unconnected-(S2-Pad2)") (class "Default")
      (node (ref "S2") (pin "2") (pinfunction "2_2") (pintype "passive"))
    )
  )
)
